# v1-mouse-pins-assigned.net
KiCad netlist of a schematic drawn in EAGLE
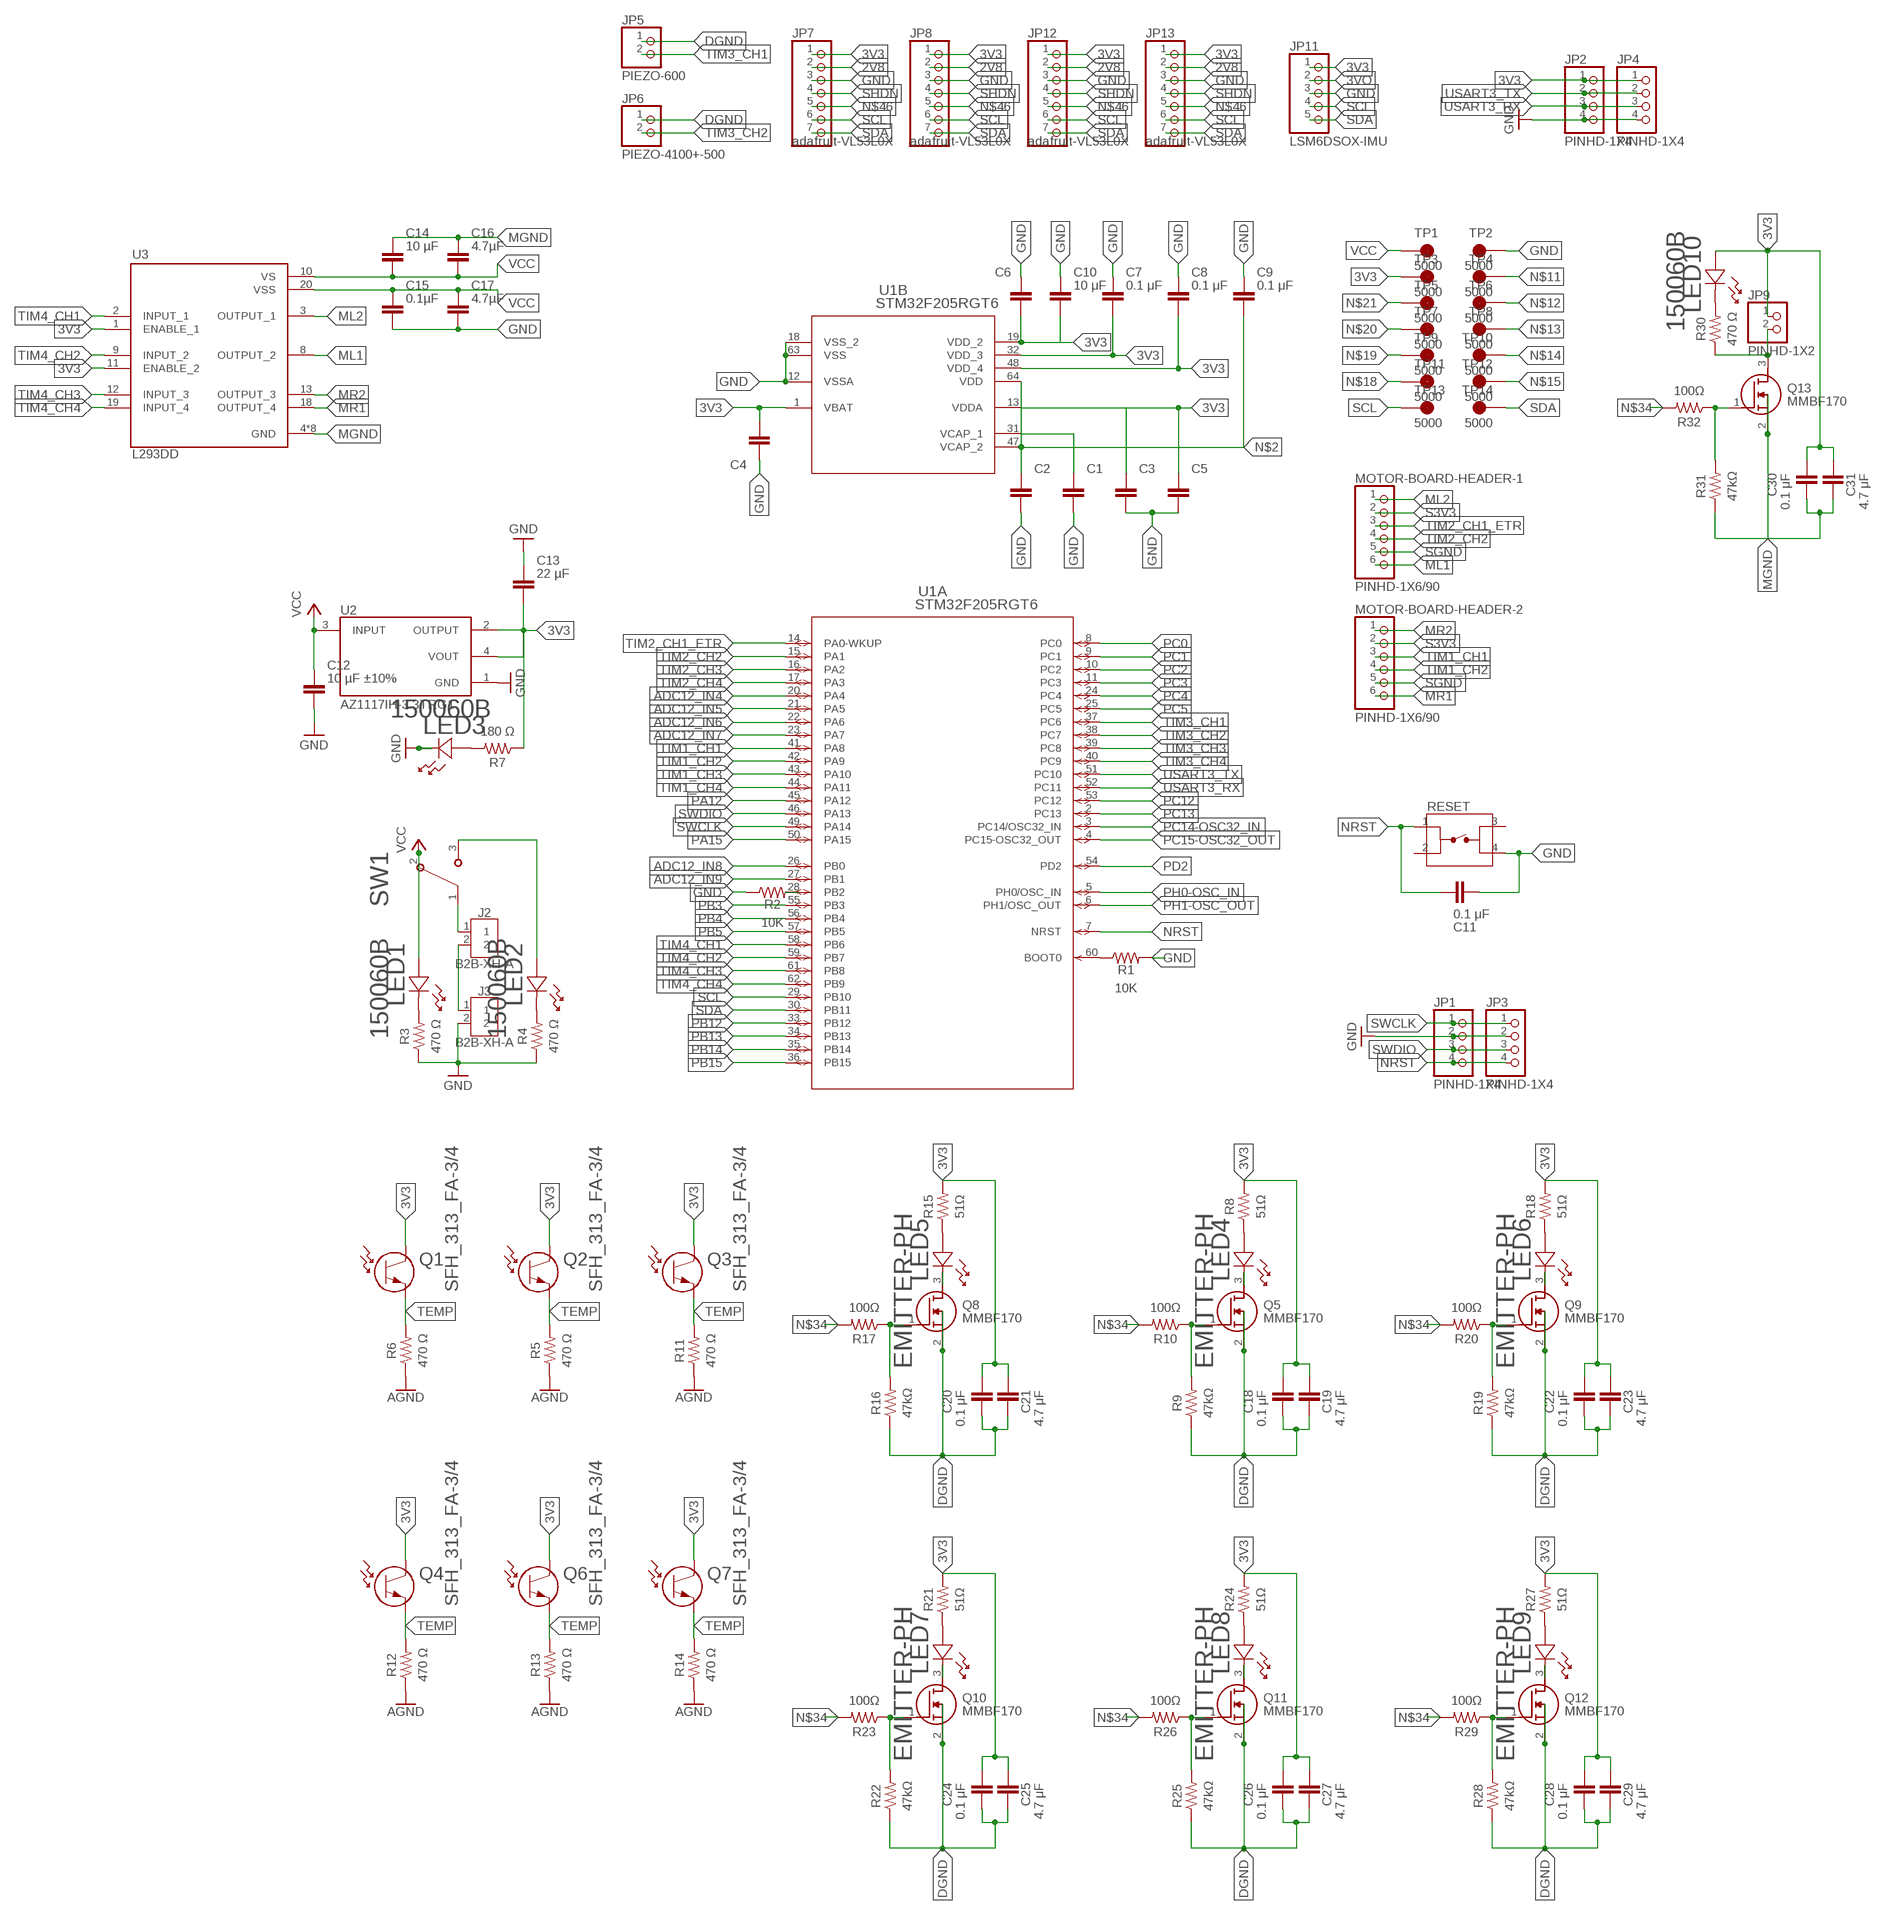
[diagram p0: schematic, sheet 1]

(export (version "E")
  (design (tool "Eeschema 10.0.6"))
  (components
    (comp (ref "C1")
      (value "2.2 μF")
      (footprint "eagle-import:CAPC1608X85")
      (libsource (lib "eagle-import") (part "CCHIP-0603(1608-METRIC)_"))
    )
    (comp (ref "C2")
      (value "2.2 μF")
      (footprint "eagle-import:CAPC1608X85")
      (libsource (lib "eagle-import") (part "CCHIP-0603(1608-METRIC)_"))
    )
    (comp (ref "C3")
      (value "0.1 μF")
      (footprint "eagle-import:CAPC1608X85")
      (libsource (lib "eagle-import") (part "CCHIP-0603(1608-METRIC)_"))
    )
    (comp (ref "C4")
      (value "0.1 μF")
      (footprint "eagle-import:CAPC1608X85")
      (libsource (lib "eagle-import") (part "CCHIP-0603(1608-METRIC)_"))
    )
    (comp (ref "C5")
      (value "1 μF")
      (footprint "eagle-import:CAPC1608X85")
      (libsource (lib "eagle-import") (part "CCHIP-0603(1608-METRIC)_"))
    )
    (comp (ref "C6")
      (value "0.1 μF")
      (footprint "eagle-import:CAPC1608X85")
      (libsource (lib "eagle-import") (part "CCHIP-0603(1608-METRIC)_"))
    )
    (comp (ref "C7")
      (value "0.1 μF")
      (footprint "eagle-import:CAPC1608X85")
      (libsource (lib "eagle-import") (part "Capacitor2_CCHIP-0603(1608-METRIC)_"))
    )
    (comp (ref "C8")
      (value "0.1 μF")
      (footprint "eagle-import:CAPC1608X85")
      (libsource (lib "eagle-import") (part "Capacitor2_CCHIP-0603(1608-METRIC)_"))
    )
    (comp (ref "C9")
      (value "0.1 μF")
      (footprint "eagle-import:CAPC1608X85")
      (libsource (lib "eagle-import") (part "Capacitor2_CCHIP-0603(1608-METRIC)_"))
    )
    (comp (ref "C10")
      (value "10 μF")
      (footprint "eagle-import:CAPC1608X85")
      (libsource (lib "eagle-import") (part "Capacitor2_CCHIP-0603(1608-METRIC)_"))
    )
    (comp (ref "C11")
      (value "0.1 μF")
      (footprint "eagle-import:CAPC1608X85")
      (libsource (lib "eagle-import") (part "Capacitor2_CCHIP-0603(1608-METRIC)_"))
    )
    (comp (ref "C12")
      (value "10 µF ±10%")
      (footprint "eagle-import:CAPC1608X85")
      (libsource (lib "eagle-import") (part "CCHIP-0603(1608-METRIC)_"))
    )
    (comp (ref "C13")
      (value "22 µF")
      (footprint "eagle-import:CAPC1608X85")
      (libsource (lib "eagle-import") (part "CCHIP-0603(1608-METRIC)_"))
    )
    (comp (ref "C14")
      (value "10 µF")
      (footprint "eagle-import:CAPC1608X85")
      (libsource (lib "eagle-import") (part "CCHIP-0603(1608-METRIC)_"))
    )
    (comp (ref "C15")
      (value "0.1µF")
      (footprint "eagle-import:CAPC1608X85")
      (libsource (lib "eagle-import") (part "CCHIP-0603(1608-METRIC)_"))
    )
    (comp (ref "C16")
      (value "4.7µF")
      (footprint "eagle-import:CAPC1608X85")
      (libsource (lib "eagle-import") (part "CCHIP-0603(1608-METRIC)_"))
    )
    (comp (ref "C17")
      (value "4.7µF")
      (footprint "eagle-import:CAPC1608X85")
      (libsource (lib "eagle-import") (part "CCHIP-0603(1608-METRIC)_"))
    )
    (comp (ref "C18")
      (value "0.1 μF")
      (footprint "eagle-import:CAPC1608X85")
      (libsource (lib "eagle-import") (part "Capacitor2_CCHIP-0603(1608-METRIC)_"))
    )
    (comp (ref "C19")
      (value "4.7 μF")
      (footprint "eagle-import:CAPC1608X85")
      (libsource (lib "eagle-import") (part "Capacitor2_CCHIP-0603(1608-METRIC)_"))
    )
    (comp (ref "C20")
      (value "0.1 μF")
      (footprint "eagle-import:CAPC1608X85")
      (libsource (lib "eagle-import") (part "Capacitor2_CCHIP-0603(1608-METRIC)_"))
    )
    (comp (ref "C21")
      (value "4.7 μF")
      (footprint "eagle-import:CAPC1608X85")
      (libsource (lib "eagle-import") (part "Capacitor2_CCHIP-0603(1608-METRIC)_"))
    )
    (comp (ref "C22")
      (value "0.1 μF")
      (footprint "eagle-import:CAPC1608X85")
      (libsource (lib "eagle-import") (part "Capacitor2_CCHIP-0603(1608-METRIC)_"))
    )
    (comp (ref "C23")
      (value "4.7 μF")
      (footprint "eagle-import:CAPC1608X85")
      (libsource (lib "eagle-import") (part "Capacitor2_CCHIP-0603(1608-METRIC)_"))
    )
    (comp (ref "C24")
      (value "0.1 μF")
      (footprint "eagle-import:CAPC1608X85")
      (libsource (lib "eagle-import") (part "Capacitor2_CCHIP-0603(1608-METRIC)_"))
    )
    (comp (ref "C25")
      (value "4.7 μF")
      (footprint "eagle-import:CAPC1608X85")
      (libsource (lib "eagle-import") (part "Capacitor2_CCHIP-0603(1608-METRIC)_"))
    )
    (comp (ref "C26")
      (value "0.1 μF")
      (footprint "eagle-import:CAPC1608X85")
      (libsource (lib "eagle-import") (part "Capacitor2_CCHIP-0603(1608-METRIC)_"))
    )
    (comp (ref "C27")
      (value "4.7 μF")
      (footprint "eagle-import:CAPC1608X85")
      (libsource (lib "eagle-import") (part "Capacitor2_CCHIP-0603(1608-METRIC)_"))
    )
    (comp (ref "C28")
      (value "0.1 μF")
      (footprint "eagle-import:CAPC1608X85")
      (libsource (lib "eagle-import") (part "Capacitor2_CCHIP-0603(1608-METRIC)_"))
    )
    (comp (ref "C29")
      (value "4.7 μF")
      (footprint "eagle-import:CAPC1608X85")
      (libsource (lib "eagle-import") (part "Capacitor2_CCHIP-0603(1608-METRIC)_"))
    )
    (comp (ref "C30")
      (value "0.1 μF")
      (footprint "eagle-import:CAPC1608X85")
      (libsource (lib "eagle-import") (part "Capacitor2_CCHIP-0603(1608-METRIC)_"))
    )
    (comp (ref "C31")
      (value "4.7 μF")
      (footprint "eagle-import:CAPC1608X85")
      (libsource (lib "eagle-import") (part "Capacitor2_CCHIP-0603(1608-METRIC)_"))
    )
    (comp (ref "J2")
      (value "B2B-XH-A")
      (footprint "eagle-import:B2B-XH-A")
      (fields
        (field (name "MANUFACTURER") "JST Sales America Inc. ")
        (field (name "MPN") "B2B-XH-A(LF)(SN) ")
      )
      (libsource (lib "eagle-import") (part "B2B-XH-A"))
    )
    (comp (ref "J3")
      (value "B2B-XH-A")
      (footprint "eagle-import:B2B-XH-A")
      (fields
        (field (name "MANUFACTURER") "JST Sales America Inc. ")
        (field (name "MPN") "B2B-XH-A(LF)(SN) ")
      )
      (libsource (lib "eagle-import") (part "B2B-XH-A"))
    )
    (comp (ref "JP1")
      (value "PINHD-1X4")
      (footprint "eagle-import:1X04")
      (fields (field (name "MANUFACTURER") "Generic"))
      (libsource (lib "eagle-import") (part "PINHD-1X4"))
    )
    (comp (ref "JP2")
      (value "PINHD-1X4")
      (footprint "eagle-import:1X04")
      (fields (field (name "MANUFACTURER") "Generic"))
      (libsource (lib "eagle-import") (part "PINHD-1X4"))
    )
    (comp (ref "JP3")
      (value "PINHD-1X4")
      (footprint "eagle-import:1X04")
      (fields (field (name "MANUFACTURER") "Generic"))
      (libsource (lib "eagle-import") (part "PINHD-1X4"))
    )
    (comp (ref "JP4")
      (value "PINHD-1X4")
      (footprint "eagle-import:1X04")
      (fields (field (name "MANUFACTURER") "Generic"))
      (libsource (lib "eagle-import") (part "PINHD-1X4"))
    )
    (comp (ref "JP5")
      (value "PIEZO-600")
      (footprint "eagle-import:1X02_90")
      (fields (field (name "MANUFACTURER") "Generic"))
      (libsource (lib "eagle-import") (part "PINHD-1X2/90"))
    )
    (comp (ref "JP6")
      (value "PIEZO-4100+-500")
      (footprint "eagle-import:1X02_90")
      (fields (field (name "MANUFACTURER") "Generic"))
      (libsource (lib "eagle-import") (part "PINHD-1X2/90"))
    )
    (comp (ref "JP7")
      (value "adafruit-VL53L0X")
      (footprint "eagle-import:1X07_90")
      (fields (field (name "MANUFACTURER") "Generic"))
      (libsource (lib "eagle-import") (part "PINHD-1X7/90"))
    )
    (comp (ref "JP8")
      (value "adafruit-VL53L0X")
      (footprint "eagle-import:1X07_90")
      (fields (field (name "MANUFACTURER") "Generic"))
      (libsource (lib "eagle-import") (part "PINHD-1X7/90"))
    )
    (comp (ref "JP9")
      (value "PINHD-1X2")
      (footprint "eagle-import:1X02")
      (fields (field (name "MANUFACTURER") "Generic"))
      (libsource (lib "eagle-import") (part "PINHD-1X2"))
    )
    (comp (ref "JP11")
      (value "LSM6DSOX-IMU")
      (footprint "eagle-import:1_05X2MM")
      (fields (field (name "MANUFACTURER") "Generic"))
      (libsource (lib "eagle-import") (part "PINHD-1X55X2MM"))
    )
    (comp (ref "JP12")
      (value "adafruit-VL53L0X")
      (footprint "eagle-import:1X07_90")
      (fields (field (name "MANUFACTURER") "Generic"))
      (libsource (lib "eagle-import") (part "PINHD-1X7/90"))
    )
    (comp (ref "JP13")
      (value "adafruit-VL53L0X")
      (footprint "eagle-import:1X07_90")
      (fields (field (name "MANUFACTURER") "Generic"))
      (libsource (lib "eagle-import") (part "PINHD-1X7/90"))
    )
    (comp (ref "LED1")
      (value "150060B")
      (footprint "eagle-import:LED_150060B_WRE-L")
      (fields
        (field (name "MANUFACTURER_PART_NUMBER") "150060VS55040")
        (field (name "COPYRIGHT") "Copyright (C) 2024 Ultra Librarian. All rights reserved.")
      )
      (libsource (lib "eagle-import") (part "150060VS55040LED_150060B_WRE-L"))
    )
    (comp (ref "LED2")
      (value "150060B")
      (footprint "eagle-import:LED_150060B_WRE-L")
      (fields
        (field (name "MANUFACTURER_PART_NUMBER") "150060VS55040")
        (field (name "COPYRIGHT") "Copyright (C) 2024 Ultra Librarian. All rights reserved.")
      )
      (libsource (lib "eagle-import") (part "150060VS55040LED_150060B_WRE-L"))
    )
    (comp (ref "LED3")
      (value "150060B")
      (footprint "eagle-import:LED_150060B_WRE-L")
      (fields
        (field (name "MANUFACTURER_PART_NUMBER") "150060VS55040")
        (field (name "COPYRIGHT") "Copyright (C) 2024 Ultra Librarian. All rights reserved.")
      )
      (libsource (lib "eagle-import") (part "150060VS55040LED_150060B_WRE-L"))
    )
    (comp (ref "LED4")
      (value "EMITTER-PH")
      (footprint "eagle-import:LED_B1911PG--20D000514U1930_01")
      (fields
        (field (name "MANUFACTURER_PART_NUMBER") "B1911PG--20D000514U1930")
        (field (name "COPYRIGHT") "Copyright (C) 2024 Ultra Librarian. All rights reserved.")
      )
      (libsource (lib "eagle-import") (part "B1911PG--20D000514U1930LED_B1911PG--20D000514U1930_01"))
    )
    (comp (ref "LED5")
      (value "EMITTER-PH")
      (footprint "eagle-import:LED_B1911PG--20D000514U1930_01")
      (fields
        (field (name "MANUFACTURER_PART_NUMBER") "B1911PG--20D000514U1930")
        (field (name "COPYRIGHT") "Copyright (C) 2024 Ultra Librarian. All rights reserved.")
      )
      (libsource (lib "eagle-import") (part "B1911PG--20D000514U1930LED_B1911PG--20D000514U1930_01"))
    )
    (comp (ref "LED6")
      (value "EMITTER-PH")
      (footprint "eagle-import:LED_B1911PG--20D000514U1930_01")
      (fields
        (field (name "MANUFACTURER_PART_NUMBER") "B1911PG--20D000514U1930")
        (field (name "COPYRIGHT") "Copyright (C) 2024 Ultra Librarian. All rights reserved.")
      )
      (libsource (lib "eagle-import") (part "B1911PG--20D000514U1930LED_B1911PG--20D000514U1930_01"))
    )
    (comp (ref "LED7")
      (value "EMITTER-PH")
      (footprint "eagle-import:LED_B1911PG--20D000514U1930_01")
      (fields
        (field (name "MANUFACTURER_PART_NUMBER") "B1911PG--20D000514U1930")
        (field (name "COPYRIGHT") "Copyright (C) 2024 Ultra Librarian. All rights reserved.")
      )
      (libsource (lib "eagle-import") (part "B1911PG--20D000514U1930LED_B1911PG--20D000514U1930_01"))
    )
    (comp (ref "LED8")
      (value "EMITTER-PH")
      (footprint "eagle-import:LED_B1911PG--20D000514U1930_01")
      (fields
        (field (name "MANUFACTURER_PART_NUMBER") "B1911PG--20D000514U1930")
        (field (name "COPYRIGHT") "Copyright (C) 2024 Ultra Librarian. All rights reserved.")
      )
      (libsource (lib "eagle-import") (part "B1911PG--20D000514U1930LED_B1911PG--20D000514U1930_01"))
    )
    (comp (ref "LED9")
      (value "EMITTER-PH")
      (footprint "eagle-import:LED_B1911PG--20D000514U1930_01")
      (fields
        (field (name "MANUFACTURER_PART_NUMBER") "B1911PG--20D000514U1930")
        (field (name "COPYRIGHT") "Copyright (C) 2024 Ultra Librarian. All rights reserved.")
      )
      (libsource (lib "eagle-import") (part "B1911PG--20D000514U1930LED_B1911PG--20D000514U1930_01"))
    )
    (comp (ref "LED10")
      (value "150060B")
      (footprint "eagle-import:LED_150060B_WRE-L")
      (fields
        (field (name "MANUFACTURER_PART_NUMBER") "150060VS55040")
        (field (name "COPYRIGHT") "Copyright (C) 2024 Ultra Librarian. All rights reserved.")
      )
      (libsource (lib "eagle-import") (part "150060VS55040LED_150060B_WRE-L"))
    )
    (comp (ref "MOTOR-BOARD-HEADER-1")
      (value "PINHD-1X6/90")
      (footprint "eagle-import:1X06_90")
      (fields (field (name "MANUFACTURER") "Generic"))
      (libsource (lib "eagle-import") (part "PINHD-1X6/90"))
    )
    (comp (ref "MOTOR-BOARD-HEADER-2")
      (value "PINHD-1X6/90")
      (footprint "eagle-import:1X06_90")
      (fields (field (name "MANUFACTURER") "Generic"))
      (libsource (lib "eagle-import") (part "PINHD-1X6/90"))
    )
    (comp (ref "Q1")
      (value "SFH_313_FA-3/4")
      (footprint "eagle-import:SFH_313_FA-3_4_OSR")
      (fields
        (field (name "MANUFACTURER_PART_NUMBER") "SFH 313 FA-3/4")
        (field (name "COPYRIGHT") "Copyright (C) 2024 Ultra Librarian. All rights reserved.")
      )
      (libsource (lib "eagle-import") (part "SFH_313_FA-3/4SFH_313_FA-3/4_OSR"))
    )
    (comp (ref "Q2")
      (value "SFH_313_FA-3/4")
      (footprint "eagle-import:SFH_313_FA-3_4_OSR")
      (fields
        (field (name "MANUFACTURER_PART_NUMBER") "SFH 313 FA-3/4")
        (field (name "COPYRIGHT") "Copyright (C) 2024 Ultra Librarian. All rights reserved.")
      )
      (libsource (lib "eagle-import") (part "SFH_313_FA-3/4SFH_313_FA-3/4_OSR"))
    )
    (comp (ref "Q3")
      (value "SFH_313_FA-3/4")
      (footprint "eagle-import:SFH_313_FA-3_4_OSR")
      (fields
        (field (name "MANUFACTURER_PART_NUMBER") "SFH 313 FA-3/4")
        (field (name "COPYRIGHT") "Copyright (C) 2024 Ultra Librarian. All rights reserved.")
      )
      (libsource (lib "eagle-import") (part "SFH_313_FA-3/4SFH_313_FA-3/4_OSR"))
    )
    (comp (ref "Q4")
      (value "SFH_313_FA-3/4")
      (footprint "eagle-import:SFH_313_FA-3_4_OSR")
      (fields
        (field (name "MANUFACTURER_PART_NUMBER") "SFH 313 FA-3/4")
        (field (name "COPYRIGHT") "Copyright (C) 2024 Ultra Librarian. All rights reserved.")
      )
      (libsource (lib "eagle-import") (part "SFH_313_FA-3/4SFH_313_FA-3/4_OSR"))
    )
    (comp (ref "Q5")
      (value "MMBF170")
      (footprint "eagle-import:SOT96P237X111-3N")
      (fields (field (name "MOUSER_PART_NUMBER") "512-MMBF170"))
      (libsource (lib "eagle-import") (part "MMBF170"))
    )
    (comp (ref "Q6")
      (value "SFH_313_FA-3/4")
      (footprint "eagle-import:SFH_313_FA-3_4_OSR")
      (fields
        (field (name "MANUFACTURER_PART_NUMBER") "SFH 313 FA-3/4")
        (field (name "COPYRIGHT") "Copyright (C) 2024 Ultra Librarian. All rights reserved.")
      )
      (libsource (lib "eagle-import") (part "SFH_313_FA-3/4SFH_313_FA-3/4_OSR"))
    )
    (comp (ref "Q7")
      (value "SFH_313_FA-3/4")
      (footprint "eagle-import:SFH_313_FA-3_4_OSR")
      (fields
        (field (name "MANUFACTURER_PART_NUMBER") "SFH 313 FA-3/4")
        (field (name "COPYRIGHT") "Copyright (C) 2024 Ultra Librarian. All rights reserved.")
      )
      (libsource (lib "eagle-import") (part "SFH_313_FA-3/4SFH_313_FA-3/4_OSR"))
    )
    (comp (ref "Q8")
      (value "MMBF170")
      (footprint "eagle-import:SOT96P237X111-3N")
      (fields (field (name "MOUSER_PART_NUMBER") "512-MMBF170"))
      (libsource (lib "eagle-import") (part "MMBF170"))
    )
    (comp (ref "Q9")
      (value "MMBF170")
      (footprint "eagle-import:SOT96P237X111-3N")
      (fields (field (name "MOUSER_PART_NUMBER") "512-MMBF170"))
      (libsource (lib "eagle-import") (part "MMBF170"))
    )
    (comp (ref "Q10")
      (value "MMBF170")
      (footprint "eagle-import:SOT96P237X111-3N")
      (fields (field (name "MOUSER_PART_NUMBER") "512-MMBF170"))
      (libsource (lib "eagle-import") (part "MMBF170"))
    )
    (comp (ref "Q11")
      (value "MMBF170")
      (footprint "eagle-import:SOT96P237X111-3N")
      (fields (field (name "MOUSER_PART_NUMBER") "512-MMBF170"))
      (libsource (lib "eagle-import") (part "MMBF170"))
    )
    (comp (ref "Q12")
      (value "MMBF170")
      (footprint "eagle-import:SOT96P237X111-3N")
      (fields (field (name "MOUSER_PART_NUMBER") "512-MMBF170"))
      (libsource (lib "eagle-import") (part "MMBF170"))
    )
    (comp (ref "Q13")
      (value "MMBF170")
      (footprint "eagle-import:SOT96P237X111-3N")
      (fields (field (name "MOUSER_PART_NUMBER") "512-MMBF170"))
      (libsource (lib "eagle-import") (part "MMBF170"))
    )
    (comp (ref "R1")
      (value "10K")
      (footprint "eagle-import:RESC1608X60")
      (libsource (lib "eagle-import") (part "Resistor2_R-USCHIP-0603(1608-METRIC)_"))
    )
    (comp (ref "R2")
      (value "10K")
      (footprint "eagle-import:RESC1608X60")
      (libsource (lib "eagle-import") (part "Resistor2_R-USCHIP-0603(1608-METRIC)_"))
    )
    (comp (ref "R3")
      (value "470 Ω")
      (footprint "eagle-import:RESC1608X60")
      (libsource (lib "eagle-import") (part "R-USCHIP-0603(1608-METRIC)_"))
    )
    (comp (ref "R4")
      (value "470 Ω")
      (footprint "eagle-import:RESC1608X60")
      (libsource (lib "eagle-import") (part "R-USCHIP-0603(1608-METRIC)_"))
    )
    (comp (ref "R5")
      (value "470 Ω")
      (footprint "eagle-import:RESC1608X60")
      (libsource (lib "eagle-import") (part "R-USCHIP-0603(1608-METRIC)_"))
    )
    (comp (ref "R6")
      (value "470 Ω")
      (footprint "eagle-import:RESC1608X60")
      (libsource (lib "eagle-import") (part "R-USCHIP-0603(1608-METRIC)_"))
    )
    (comp (ref "R7")
      (value "180 Ω")
      (footprint "eagle-import:RESC1608X60")
      (libsource (lib "eagle-import") (part "R-USCHIP-0603(1608-METRIC)_"))
    )
    (comp (ref "R8")
      (value "51Ω")
      (footprint "eagle-import:RESC1608X60")
      (libsource (lib "eagle-import") (part "R-USCHIP-0603(1608-METRIC)_"))
    )
    (comp (ref "R9")
      (value "47kΩ")
      (footprint "eagle-import:RESC1608X60")
      (libsource (lib "eagle-import") (part "R-USCHIP-0603(1608-METRIC)_"))
    )
    (comp (ref "R10")
      (value "100Ω")
      (footprint "eagle-import:RESC1608X60")
      (libsource (lib "eagle-import") (part "R-USCHIP-0603(1608-METRIC)_"))
    )
    (comp (ref "R11")
      (value "470 Ω")
      (footprint "eagle-import:RESC1608X60")
      (libsource (lib "eagle-import") (part "R-USCHIP-0603(1608-METRIC)_"))
    )
    (comp (ref "R12")
      (value "470 Ω")
      (footprint "eagle-import:RESC1608X60")
      (libsource (lib "eagle-import") (part "R-USCHIP-0603(1608-METRIC)_"))
    )
    (comp (ref "R13")
      (value "470 Ω")
      (footprint "eagle-import:RESC1608X60")
      (libsource (lib "eagle-import") (part "R-USCHIP-0603(1608-METRIC)_"))
    )
    (comp (ref "R14")
      (value "470 Ω")
      (footprint "eagle-import:RESC1608X60")
      (libsource (lib "eagle-import") (part "R-USCHIP-0603(1608-METRIC)_"))
    )
    (comp (ref "R15")
      (value "51Ω")
      (footprint "eagle-import:RESC1608X60")
      (libsource (lib "eagle-import") (part "R-USCHIP-0603(1608-METRIC)_"))
    )
    (comp (ref "R16")
      (value "47kΩ")
      (footprint "eagle-import:RESC1608X60")
      (libsource (lib "eagle-import") (part "R-USCHIP-0603(1608-METRIC)_"))
    )
    (comp (ref "R17")
      (value "100Ω")
      (footprint "eagle-import:RESC1608X60")
      (libsource (lib "eagle-import") (part "R-USCHIP-0603(1608-METRIC)_"))
    )
    (comp (ref "R18")
      (value "51Ω")
      (footprint "eagle-import:RESC1608X60")
      (libsource (lib "eagle-import") (part "R-USCHIP-0603(1608-METRIC)_"))
    )
    (comp (ref "R19")
      (value "47kΩ")
      (footprint "eagle-import:RESC1608X60")
      (libsource (lib "eagle-import") (part "R-USCHIP-0603(1608-METRIC)_"))
    )
    (comp (ref "R20")
      (value "100Ω")
      (footprint "eagle-import:RESC1608X60")
      (libsource (lib "eagle-import") (part "R-USCHIP-0603(1608-METRIC)_"))
    )
    (comp (ref "R21")
      (value "51Ω")
      (footprint "eagle-import:RESC1608X60")
      (libsource (lib "eagle-import") (part "R-USCHIP-0603(1608-METRIC)_"))
    )
    (comp (ref "R22")
      (value "47kΩ")
      (footprint "eagle-import:RESC1608X60")
      (libsource (lib "eagle-import") (part "R-USCHIP-0603(1608-METRIC)_"))
    )
    (comp (ref "R23")
      (value "100Ω")
      (footprint "eagle-import:RESC1608X60")
      (libsource (lib "eagle-import") (part "R-USCHIP-0603(1608-METRIC)_"))
    )
    (comp (ref "R24")
      (value "51Ω")
      (footprint "eagle-import:RESC1608X60")
      (libsource (lib "eagle-import") (part "R-USCHIP-0603(1608-METRIC)_"))
    )
    (comp (ref "R25")
      (value "47kΩ")
      (footprint "eagle-import:RESC1608X60")
      (libsource (lib "eagle-import") (part "R-USCHIP-0603(1608-METRIC)_"))
    )
    (comp (ref "R26")
      (value "100Ω")
      (footprint "eagle-import:RESC1608X60")
      (libsource (lib "eagle-import") (part "R-USCHIP-0603(1608-METRIC)_"))
    )
    (comp (ref "R27")
      (value "51Ω")
      (footprint "eagle-import:RESC1608X60")
      (libsource (lib "eagle-import") (part "R-USCHIP-0603(1608-METRIC)_"))
    )
    (comp (ref "R28")
      (value "47kΩ")
      (footprint "eagle-import:RESC1608X60")
      (libsource (lib "eagle-import") (part "R-USCHIP-0603(1608-METRIC)_"))
    )
    (comp (ref "R29")
      (value "100Ω")
      (footprint "eagle-import:RESC1608X60")
      (libsource (lib "eagle-import") (part "R-USCHIP-0603(1608-METRIC)_"))
    )
    (comp (ref "R30")
      (value "470 Ω")
      (footprint "eagle-import:RESC1608X60")
      (libsource (lib "eagle-import") (part "R-USCHIP-0603(1608-METRIC)_"))
    )
    (comp (ref "R31")
      (value "47kΩ")
      (footprint "eagle-import:RESC1608X60")
      (libsource (lib "eagle-import") (part "R-USCHIP-0603(1608-METRIC)_"))
    )
    (comp (ref "R32")
      (value "100Ω")
      (footprint "eagle-import:RESC1608X60")
      (libsource (lib "eagle-import") (part "R-USCHIP-0603(1608-METRIC)_"))
    )
    (comp (ref "RESET")
      (value "FSM4JSMA")
      (footprint "eagle-import:TE_FSM4JSMA")
      (fields
        (field (name "COMMENT") "4-1437565-1")
        (field (name "DIGI-KEY_PART_NUMBER") "450-1759-2-ND")
        (field (name "MF") "TE Connectivity")
      )
      (libsource (lib "eagle-import") (part "FSM4JSMA"))
    )
    (comp (ref "SW1")
      (value "EG1218SW_1218_EWI")
      (footprint "eagle-import:SW_1218_EWI")
      (fields
        (field (name "MANUFACTURER_PART_NUMBER") "EG1218")
        (field (name "COPYRIGHT") "Copyright (C) 2024 Ultra Librarian. All rights reserved.")
      )
      (libsource (lib "eagle-import") (part "EG1218SW_1218_EWI"))
    )
    (comp (ref "TP1")
      (value "5000")
      (footprint "eagle-import:KEYSTONE_5000")
      (fields (field (name "MF") "Keystone Electronics"))
      (libsource (lib "eagle-import") (part "5000"))
    )
    (comp (ref "TP2")
      (value "5000")
      (footprint "eagle-import:KEYSTONE_5000")
      (fields (field (name "MF") "Keystone Electronics"))
      (libsource (lib "eagle-import") (part "5000"))
    )
    (comp (ref "TP3")
      (value "5000")
      (footprint "eagle-import:KEYSTONE_5000")
      (fields (field (name "MF") "Keystone Electronics"))
      (libsource (lib "eagle-import") (part "5000"))
    )
    (comp (ref "TP4")
      (value "5000")
      (footprint "eagle-import:KEYSTONE_5000")
      (fields (field (name "MF") "Keystone Electronics"))
      (libsource (lib "eagle-import") (part "5000"))
    )
    (comp (ref "TP5")
      (value "5000")
      (footprint "eagle-import:KEYSTONE_5000")
      (fields (field (name "MF") "Keystone Electronics"))
      (libsource (lib "eagle-import") (part "5000"))
    )
    (comp (ref "TP6")
      (value "5000")
      (footprint "eagle-import:KEYSTONE_5000")
      (fields (field (name "MF") "Keystone Electronics"))
      (libsource (lib "eagle-import") (part "5000"))
    )
    (comp (ref "TP7")
      (value "5000")
      (footprint "eagle-import:KEYSTONE_5000")
      (fields (field (name "MF") "Keystone Electronics"))
      (libsource (lib "eagle-import") (part "5000"))
    )
    (comp (ref "TP8")
      (value "5000")
      (footprint "eagle-import:KEYSTONE_5000")
      (fields (field (name "MF") "Keystone Electronics"))
      (libsource (lib "eagle-import") (part "5000"))
    )
    (comp (ref "TP9")
      (value "5000")
      (footprint "eagle-import:KEYSTONE_5000")
      (fields (field (name "MF") "Keystone Electronics"))
      (libsource (lib "eagle-import") (part "5000"))
    )
    (comp (ref "TP10")
      (value "5000")
      (footprint "eagle-import:KEYSTONE_5000")
      (fields (field (name "MF") "Keystone Electronics"))
      (libsource (lib "eagle-import") (part "5000"))
    )
    (comp (ref "TP11")
      (value "5000")
      (footprint "eagle-import:KEYSTONE_5000")
      (fields (field (name "MF") "Keystone Electronics"))
      (libsource (lib "eagle-import") (part "5000"))
    )
    (comp (ref "TP12")
      (value "5000")
      (footprint "eagle-import:KEYSTONE_5000")
      (fields (field (name "MF") "Keystone Electronics"))
      (libsource (lib "eagle-import") (part "5000"))
    )
    (comp (ref "TP13")
      (value "5000")
      (footprint "eagle-import:KEYSTONE_5000")
      (fields (field (name "MF") "Keystone Electronics"))
      (libsource (lib "eagle-import") (part "5000"))
    )
    (comp (ref "TP14")
      (value "5000")
      (footprint "eagle-import:KEYSTONE_5000")
      (fields (field (name "MF") "Keystone Electronics"))
      (libsource (lib "eagle-import") (part "5000"))
    )
    (comp (ref "U1")
      (value "STM32F205RGT6")
      (footprint "eagle-import:LQFP64-10X10MM")
      (fields (field (name "COPYRIGHT") "Copyright (C) 2021 Ultra Librarian. All rights reserved."))
      (libsource (lib "eagle-import") (part "STM32F205RGT6"))
    )
    (comp (ref "U2")
      (value "AZ1117IH-3.3TRG1")
      (footprint "eagle-import:SOT230P700X185-4N")
      (fields (field (name "MF") "Diodes Inc."))
      (libsource (lib "eagle-import") (part "AZ1117IH-3.3TRG1"))
    )
    (comp (ref "U3")
      (value "L293DD")
      (footprint "eagle-import:SOIC127P1032X265-20N")
      (fields (field (name "MANUFACTURER") "STMicroelectronics"))
      (libsource (lib "eagle-import") (part "L293DD"))
    )
  )
  (nets
    (net (code "1") (name "2V8") (class "Default")
      (node (ref "JP12") (pin "2") (pinfunction "2_2") (pintype "passive"))
      (node (ref "JP13") (pin "2") (pinfunction "2_2") (pintype "passive"))
      (node (ref "JP7") (pin "2") (pinfunction "2_2") (pintype "passive"))
      (node (ref "JP8") (pin "2") (pinfunction "2_2") (pintype "passive"))
    )
    (net (code "2") (name "3V3") (class "Default")
      (node (ref "C10") (pin "2") (pinfunction "2_2") (pintype "passive"))
      (node (ref "C13") (pin "2") (pinfunction "2_2") (pintype "passive"))
      (node (ref "C18") (pin "2") (pinfunction "2_2") (pintype "passive"))
      (node (ref "C19") (pin "2") (pinfunction "2_2") (pintype "passive"))
      (node (ref "C20") (pin "2") (pinfunction "2_2") (pintype "passive"))
      (node (ref "C21") (pin "2") (pinfunction "2_2") (pintype "passive"))
      (node (ref "C22") (pin "2") (pinfunction "2_2") (pintype "passive"))
      (node (ref "C23") (pin "2") (pinfunction "2_2") (pintype "passive"))
      (node (ref "C24") (pin "2") (pinfunction "2_2") (pintype "passive"))
      (node (ref "C25") (pin "2") (pinfunction "2_2") (pintype "passive"))
      (node (ref "C26") (pin "2") (pinfunction "2_2") (pintype "passive"))
      (node (ref "C27") (pin "2") (pinfunction "2_2") (pintype "passive"))
      (node (ref "C28") (pin "2") (pinfunction "2_2") (pintype "passive"))
      (node (ref "C29") (pin "2") (pinfunction "2_2") (pintype "passive"))
      (node (ref "C3") (pin "1") (pinfunction "1_1") (pintype "passive"))
      (node (ref "C30") (pin "2") (pinfunction "2_2") (pintype "passive"))
      (node (ref "C31") (pin "2") (pinfunction "2_2") (pintype "passive"))
      (node (ref "C4") (pin "2") (pinfunction "2_2") (pintype "passive"))
      (node (ref "C5") (pin "1") (pinfunction "1_1") (pintype "passive"))
      (node (ref "C6") (pin "2") (pinfunction "2_2") (pintype "passive"))
      (node (ref "C7") (pin "2") (pinfunction "2_2") (pintype "passive"))
      (node (ref "C8") (pin "2") (pinfunction "2_2") (pintype "passive"))
      (node (ref "JP11") (pin "1") (pinfunction "1_1") (pintype "passive"))
      (node (ref "JP12") (pin "1") (pinfunction "1_1") (pintype "passive"))
      (node (ref "JP13") (pin "1") (pinfunction "1_1") (pintype "passive"))
      (node (ref "JP2") (pin "1") (pinfunction "1_1") (pintype "passive"))
      (node (ref "JP4") (pin "1") (pinfunction "1_1") (pintype "passive"))
      (node (ref "JP7") (pin "1") (pinfunction "1_1") (pintype "passive"))
      (node (ref "JP8") (pin "1") (pinfunction "1_1") (pintype "passive"))
      (node (ref "JP9") (pin "1") (pinfunction "1_1") (pintype "passive"))
      (node (ref "LED10") (pin "2") (pinfunction "2_2") (pintype "passive"))
      (node (ref "Q1") (pin "2") (pinfunction "2_2") (pintype "passive"))
      (node (ref "Q2") (pin "2") (pinfunction "2_2") (pintype "passive"))
      (node (ref "Q3") (pin "2") (pinfunction "2_2") (pintype "passive"))
      (node (ref "Q4") (pin "2") (pinfunction "2_2") (pintype "passive"))
      (node (ref "Q6") (pin "2") (pinfunction "2_2") (pintype "passive"))
      (node (ref "Q7") (pin "2") (pinfunction "2_2") (pintype "passive"))
      (node (ref "R15") (pin "2") (pinfunction "2_2") (pintype "passive"))
      (node (ref "R18") (pin "2") (pinfunction "2_2") (pintype "passive"))
      (node (ref "R21") (pin "2") (pinfunction "2_2") (pintype "passive"))
      (node (ref "R24") (pin "2") (pinfunction "2_2") (pintype "passive"))
      (node (ref "R27") (pin "2") (pinfunction "2_2") (pintype "passive"))
      (node (ref "R7") (pin "1") (pinfunction "1_1") (pintype "passive"))
      (node (ref "R8") (pin "2") (pinfunction "2_2") (pintype "passive"))
      (node (ref "TP3") (pin "TP") (pinfunction "TP_TP") (pintype "passive"))
      (node (ref "U1") (pin "1") (pinfunction "VBAT_1") (pintype "power_in"))
      (node (ref "U1") (pin "13") (pinfunction "VDDA_13") (pintype "power_in"))
      (node (ref "U1") (pin "19") (pinfunction "VDD_2_19") (pintype "power_in"))
      (node (ref "U1") (pin "32") (pinfunction "VDD_3_32") (pintype "power_in"))
      (node (ref "U1") (pin "48") (pinfunction "VDD_4_48") (pintype "power_in"))
      (node (ref "U2") (pin "2") (pinfunction "OUTPUT_2") (pintype "output"))
      (node (ref "U2") (pin "4") (pinfunction "VOUT_4") (pintype "output"))
      (node (ref "U3") (pin "1") (pinfunction "ENABLE_1_1") (pintype "input"))
      (node (ref "U3") (pin "11") (pinfunction "ENABLE_2_11") (pintype "input"))
    )
    (net (code "3") (name "3VO") (class "Default")
      (node (ref "JP11") (pin "2") (pinfunction "2_2") (pintype "passive"))
    )
    (net (code "4") (name "ADC12_IN4") (class "Default")
      (node (ref "U1") (pin "20") (pinfunction "PA4_20") (pintype "bidirectional"))
    )
    (net (code "5") (name "ADC12_IN5") (class "Default")
      (node (ref "U1") (pin "21") (pinfunction "PA5_21") (pintype "bidirectional"))
    )
    (net (code "6") (name "ADC12_IN6") (class "Default")
      (node (ref "U1") (pin "22") (pinfunction "PA6_22") (pintype "bidirectional"))
    )
    (net (code "7") (name "ADC12_IN7") (class "Default")
      (node (ref "U1") (pin "23") (pinfunction "PA7_23") (pintype "bidirectional"))
    )
    (net (code "8") (name "ADC12_IN8") (class "Default")
      (node (ref "U1") (pin "26") (pinfunction "PB0_26") (pintype "bidirectional"))
    )
    (net (code "9") (name "ADC12_IN9") (class "Default")
      (node (ref "U1") (pin "27") (pinfunction "PB1_27") (pintype "bidirectional"))
    )
    (net (code "10") (name "AGND") (class "Default")
      (node (ref "R11") (pin "1") (pinfunction "1_1") (pintype "passive"))
      (node (ref "R12") (pin "1") (pinfunction "1_1") (pintype "passive"))
      (node (ref "R13") (pin "1") (pinfunction "1_1") (pintype "passive"))
      (node (ref "R14") (pin "1") (pinfunction "1_1") (pintype "passive"))
      (node (ref "R5") (pin "1") (pinfunction "1_1") (pintype "passive"))
      (node (ref "R6") (pin "1") (pinfunction "1_1") (pintype "passive"))
    )
    (net (code "11") (name "DGND") (class "Default")
      (node (ref "C18") (pin "1") (pinfunction "1_1") (pintype "passive"))
      (node (ref "C19") (pin "1") (pinfunction "1_1") (pintype "passive"))
      (node (ref "C20") (pin "1") (pinfunction "1_1") (pintype "passive"))
      (node (ref "C21") (pin "1") (pinfunction "1_1") (pintype "passive"))
      (node (ref "C22") (pin "1") (pinfunction "1_1") (pintype "passive"))
      (node (ref "C23") (pin "1") (pinfunction "1_1") (pintype "passive"))
      (node (ref "C24") (pin "1") (pinfunction "1_1") (pintype "passive"))
      (node (ref "C25") (pin "1") (pinfunction "1_1") (pintype "passive"))
      (node (ref "C26") (pin "1") (pinfunction "1_1") (pintype "passive"))
      (node (ref "C27") (pin "1") (pinfunction "1_1") (pintype "passive"))
      (node (ref "C28") (pin "1") (pinfunction "1_1") (pintype "passive"))
      (node (ref "C29") (pin "1") (pinfunction "1_1") (pintype "passive"))
      (node (ref "C30") (pin "1") (pinfunction "1_1") (pintype "passive"))
      (node (ref "C31") (pin "1") (pinfunction "1_1") (pintype "passive"))
      (node (ref "JP5") (pin "1") (pinfunction "1_1") (pintype "passive"))
      (node (ref "JP6") (pin "1") (pinfunction "1_1") (pintype "passive"))
      (node (ref "Q10") (pin "2") (pinfunction "S_2") (pintype "bidirectional"))
      (node (ref "Q11") (pin "2") (pinfunction "S_2") (pintype "bidirectional"))
      (node (ref "Q12") (pin "2") (pinfunction "S_2") (pintype "bidirectional"))
      (node (ref "Q5") (pin "2") (pinfunction "S_2") (pintype "bidirectional"))
      (node (ref "Q8") (pin "2") (pinfunction "S_2") (pintype "bidirectional"))
      (node (ref "Q9") (pin "2") (pinfunction "S_2") (pintype "bidirectional"))
      (node (ref "R16") (pin "1") (pinfunction "1_1") (pintype "passive"))
      (node (ref "R19") (pin "1") (pinfunction "1_1") (pintype "passive"))
      (node (ref "R22") (pin "1") (pinfunction "1_1") (pintype "passive"))
      (node (ref "R25") (pin "1") (pinfunction "1_1") (pintype "passive"))
      (node (ref "R28") (pin "1") (pinfunction "1_1") (pintype "passive"))
      (node (ref "R31") (pin "1") (pinfunction "1_1") (pintype "passive"))
      (node (ref "R9") (pin "1") (pinfunction "1_1") (pintype "passive"))
    )
    (net (code "12") (name "GND") (class "Default")
      (node (ref "C1") (pin "2") (pinfunction "2_2") (pintype "passive"))
      (node (ref "C10") (pin "1") (pinfunction "1_1") (pintype "passive"))
      (node (ref "C11") (pin "1") (pinfunction "1_1") (pintype "passive"))
      (node (ref "C12") (pin "2") (pinfunction "2_2") (pintype "passive"))
      (node (ref "C13") (pin "1") (pinfunction "1_1") (pintype "passive"))
      (node (ref "C15") (pin "2") (pinfunction "2_2") (pintype "passive"))
      (node (ref "C17") (pin "2") (pinfunction "2_2") (pintype "passive"))
      (node (ref "C2") (pin "2") (pinfunction "2_2") (pintype "passive"))
      (node (ref "C3") (pin "2") (pinfunction "2_2") (pintype "passive"))
      (node (ref "C4") (pin "1") (pinfunction "1_1") (pintype "passive"))
      (node (ref "C5") (pin "2") (pinfunction "2_2") (pintype "passive"))
      (node (ref "C6") (pin "1") (pinfunction "1_1") (pintype "passive"))
      (node (ref "C7") (pin "1") (pinfunction "1_1") (pintype "passive"))
      (node (ref "C8") (pin "1") (pinfunction "1_1") (pintype "passive"))
      (node (ref "C9") (pin "1") (pinfunction "1_1") (pintype "passive"))
      (node (ref "J3") (pin "2") (pinfunction "2_2") (pintype "bidirectional"))
      (node (ref "JP1") (pin "2") (pinfunction "2_2") (pintype "passive"))
      (node (ref "JP11") (pin "3") (pinfunction "3_3") (pintype "passive"))
      (node (ref "JP12") (pin "3") (pinfunction "3_3") (pintype "passive"))
      (node (ref "JP13") (pin "3") (pinfunction "3_3") (pintype "passive"))
      (node (ref "JP2") (pin "4") (pinfunction "4_4") (pintype "passive"))
      (node (ref "JP3") (pin "2") (pinfunction "2_2") (pintype "passive"))
      (node (ref "JP4") (pin "4") (pinfunction "4_4") (pintype "passive"))
      (node (ref "JP7") (pin "3") (pinfunction "3_3") (pintype "passive"))
      (node (ref "JP8") (pin "3") (pinfunction "3_3") (pintype "passive"))
      (node (ref "LED3") (pin "1") (pinfunction "1_1") (pintype "passive"))
      (node (ref "R1") (pin "2") (pinfunction "2_2") (pintype "passive"))
      (node (ref "R2") (pin "1") (pinfunction "1_1") (pintype "passive"))
      (node (ref "R3") (pin "1") (pinfunction "1_1") (pintype "passive"))
      (node (ref "R4") (pin "1") (pinfunction "1_1") (pintype "passive"))
      (node (ref "RESET") (pin "4") (pinfunction "4_4") (pintype "passive"))
      (node (ref "TP2") (pin "TP") (pinfunction "TP_TP") (pintype "passive"))
      (node (ref "U1") (pin "12") (pinfunction "VSSA_12") (pintype "power_in"))
      (node (ref "U1") (pin "18") (pinfunction "VSS_2_18") (pintype "power_in"))
      (node (ref "U1") (pin "63") (pinfunction "VSS_63") (pintype "power_in"))
      (node (ref "U2") (pin "1") (pinfunction "GND_1") (pintype "power_in"))
    )
    (net (code "13") (name "MGND") (class "Default")
      (node (ref "C14") (pin "1") (pinfunction "1_1") (pintype "passive"))
      (node (ref "C16") (pin "1") (pinfunction "1_1") (pintype "passive"))
      (node (ref "Q13") (pin "2") (pinfunction "S_2") (pintype "bidirectional"))
      (node (ref "U3") (pin "14") (pinfunction "GND_14") (pintype "power_in"))
      (node (ref "U3") (pin "15") (pinfunction "GND_15") (pintype "power_in"))
      (node (ref "U3") (pin "16") (pinfunction "GND_16") (pintype "power_in"))
      (node (ref "U3") (pin "17") (pinfunction "GND_17") (pintype "power_in"))
      (node (ref "U3") (pin "4") (pinfunction "GND_4") (pintype "power_in"))
      (node (ref "U3") (pin "5") (pinfunction "GND_5") (pintype "power_in"))
      (node (ref "U3") (pin "6") (pinfunction "GND_6") (pintype "power_in"))
      (node (ref "U3") (pin "7") (pinfunction "GND_7") (pintype "power_in"))
    )
    (net (code "14") (name "ML1") (class "Default")
      (node (ref "MOTOR-BOARD-HEADER-1") (pin "6") (pinfunction "6_6") (pintype "passive"))
      (node (ref "U3") (pin "8") (pinfunction "OUTPUT_2_8") (pintype "output"))
    )
    (net (code "15") (name "ML2") (class "Default")
      (node (ref "MOTOR-BOARD-HEADER-1") (pin "1") (pinfunction "1_1") (pintype "passive"))
      (node (ref "U3") (pin "3") (pinfunction "OUTPUT_1_3") (pintype "output"))
    )
    (net (code "16") (name "MR1") (class "Default")
      (node (ref "MOTOR-BOARD-HEADER-2") (pin "6") (pinfunction "6_6") (pintype "passive"))
      (node (ref "U3") (pin "18") (pinfunction "OUTPUT_4_18") (pintype "output"))
    )
    (net (code "17") (name "MR2") (class "Default")
      (node (ref "MOTOR-BOARD-HEADER-2") (pin "1") (pinfunction "1_1") (pintype "passive"))
      (node (ref "U3") (pin "13") (pinfunction "OUTPUT_3_13") (pintype "output"))
    )
    (net (code "18") (name "N$2") (class "Default")
      (node (ref "C2") (pin "1") (pinfunction "1_1") (pintype "passive"))
      (node (ref "C9") (pin "2") (pinfunction "2_2") (pintype "passive"))
      (node (ref "U1") (pin "47") (pinfunction "VCAP_2_47") (pintype "power_in"))
      (node (ref "U1") (pin "64") (pinfunction "VDD_64") (pintype "power_in"))
    )
    (net (code "19") (name "N$11") (class "Default")
      (node (ref "TP4") (pin "TP") (pinfunction "TP_TP") (pintype "passive"))
    )
    (net (code "20") (name "N$12") (class "Default")
      (node (ref "TP6") (pin "TP") (pinfunction "TP_TP") (pintype "passive"))
    )
    (net (code "21") (name "N$13") (class "Default")
      (node (ref "TP8") (pin "TP") (pinfunction "TP_TP") (pintype "passive"))
    )
    (net (code "22") (name "N$14") (class "Default")
      (node (ref "TP10") (pin "TP") (pinfunction "TP_TP") (pintype "passive"))
    )
    (net (code "23") (name "N$15") (class "Default")
      (node (ref "TP12") (pin "TP") (pinfunction "TP_TP") (pintype "passive"))
    )
    (net (code "24") (name "N$18") (class "Default")
      (node (ref "TP11") (pin "TP") (pinfunction "TP_TP") (pintype "passive"))
    )
    (net (code "25") (name "N$19") (class "Default")
      (node (ref "TP9") (pin "TP") (pinfunction "TP_TP") (pintype "passive"))
    )
    (net (code "26") (name "N$20") (class "Default")
      (node (ref "TP7") (pin "TP") (pinfunction "TP_TP") (pintype "passive"))
    )
    (net (code "27") (name "N$21") (class "Default")
      (node (ref "TP5") (pin "TP") (pinfunction "TP_TP") (pintype "passive"))
    )
    (net (code "28") (name "N$34") (class "Default")
      (node (ref "R10") (pin "2") (pinfunction "2_2") (pintype "passive"))
      (node (ref "R17") (pin "2") (pinfunction "2_2") (pintype "passive"))
      (node (ref "R20") (pin "2") (pinfunction "2_2") (pintype "passive"))
      (node (ref "R23") (pin "2") (pinfunction "2_2") (pintype "passive"))
      (node (ref "R26") (pin "2") (pinfunction "2_2") (pintype "passive"))
      (node (ref "R29") (pin "2") (pinfunction "2_2") (pintype "passive"))
      (node (ref "R32") (pin "2") (pinfunction "2_2") (pintype "passive"))
    )
    (net (code "29") (name "N$46") (class "Default")
      (node (ref "JP12") (pin "5") (pinfunction "5_5") (pintype "passive"))
      (node (ref "JP13") (pin "5") (pinfunction "5_5") (pintype "passive"))
      (node (ref "JP7") (pin "5") (pinfunction "5_5") (pintype "passive"))
      (node (ref "JP8") (pin "5") (pinfunction "5_5") (pintype "passive"))
    )
    (net (code "30") (name "NRST") (class "Default")
      (node (ref "C11") (pin "2") (pinfunction "2_2") (pintype "passive"))
      (node (ref "JP1") (pin "4") (pinfunction "4_4") (pintype "passive"))
      (node (ref "JP3") (pin "4") (pinfunction "4_4") (pintype "passive"))
      (node (ref "RESET") (pin "1") (pinfunction "1_1") (pintype "passive"))
      (node (ref "U1") (pin "7") (pinfunction "NRST_7") (pintype "bidirectional"))
    )
    (net (code "31") (name "Net-(J2-Pad1)") (class "Default")
      (node (ref "J2") (pin "1") (pinfunction "1_1") (pintype "bidirectional"))
      (node (ref "SW1") (pin "1") (pinfunction "1_1") (pintype "passive"))
    )
    (net (code "32") (name "Net-(J2-Pad2)") (class "Default")
      (node (ref "J2") (pin "2") (pinfunction "2_2") (pintype "bidirectional"))
      (node (ref "J3") (pin "1") (pinfunction "1_1") (pintype "bidirectional"))
    )
    (net (code "33") (name "Net-(LED1-Pad1)") (class "Default")
      (node (ref "LED1") (pin "1") (pinfunction "1_1") (pintype "passive"))
      (node (ref "R3") (pin "2") (pinfunction "2_2") (pintype "passive"))
    )
    (net (code "34") (name "Net-(LED2-Pad1)") (class "Default")
      (node (ref "LED2") (pin "1") (pinfunction "1_1") (pintype "passive"))
      (node (ref "R4") (pin "2") (pinfunction "2_2") (pintype "passive"))
    )
    (net (code "35") (name "Net-(LED2-Pad2)") (class "Default")
      (node (ref "LED2") (pin "2") (pinfunction "2_2") (pintype "passive"))
      (node (ref "SW1") (pin "3") (pinfunction "3_3") (pintype "passive"))
    )
    (net (code "36") (name "Net-(LED3-Pad2)") (class "Default")
      (node (ref "LED3") (pin "2") (pinfunction "2_2") (pintype "passive"))
      (node (ref "R7") (pin "2") (pinfunction "2_2") (pintype "passive"))
    )
    (net (code "37") (name "Net-(LED4-Pad2)") (class "Default")
      (node (ref "LED4") (pin "2") (pinfunction "2_2") (pintype "passive"))
      (node (ref "R8") (pin "1") (pinfunction "1_1") (pintype "passive"))
    )
    (net (code "38") (name "Net-(LED5-Pad2)") (class "Default")
      (node (ref "LED5") (pin "2") (pinfunction "2_2") (pintype "passive"))
      (node (ref "R15") (pin "1") (pinfunction "1_1") (pintype "passive"))
    )
    (net (code "39") (name "Net-(LED6-Pad2)") (class "Default")
      (node (ref "LED6") (pin "2") (pinfunction "2_2") (pintype "passive"))
      (node (ref "R18") (pin "1") (pinfunction "1_1") (pintype "passive"))
    )
    (net (code "40") (name "Net-(LED7-Pad2)") (class "Default")
      (node (ref "LED7") (pin "2") (pinfunction "2_2") (pintype "passive"))
      (node (ref "R21") (pin "1") (pinfunction "1_1") (pintype "passive"))
    )
    (net (code "41") (name "Net-(LED8-Pad2)") (class "Default")
      (node (ref "LED8") (pin "2") (pinfunction "2_2") (pintype "passive"))
      (node (ref "R24") (pin "1") (pinfunction "1_1") (pintype "passive"))
    )
    (net (code "42") (name "Net-(LED9-Pad2)") (class "Default")
      (node (ref "LED9") (pin "2") (pinfunction "2_2") (pintype "passive"))
      (node (ref "R27") (pin "1") (pinfunction "1_1") (pintype "passive"))
    )
    (net (code "43") (name "Net-(LED10-Pad1)") (class "Default")
      (node (ref "LED10") (pin "1") (pinfunction "1_1") (pintype "passive"))
      (node (ref "R30") (pin "2") (pinfunction "2_2") (pintype "passive"))
    )
    (net (code "44") (name "Net-(Q5-D)") (class "Default")
      (node (ref "LED4") (pin "1") (pinfunction "1_1") (pintype "passive"))
      (node (ref "Q5") (pin "3") (pinfunction "D_3") (pintype "bidirectional"))
    )
    (net (code "45") (name "Net-(Q5-G)") (class "Default")
      (node (ref "Q5") (pin "1") (pinfunction "G_1") (pintype "bidirectional"))
      (node (ref "R10") (pin "1") (pinfunction "1_1") (pintype "passive"))
      (node (ref "R9") (pin "2") (pinfunction "2_2") (pintype "passive"))
    )
    (net (code "46") (name "Net-(Q8-D)") (class "Default")
      (node (ref "LED5") (pin "1") (pinfunction "1_1") (pintype "passive"))
      (node (ref "Q8") (pin "3") (pinfunction "D_3") (pintype "bidirectional"))
    )
    (net (code "47") (name "Net-(Q8-G)") (class "Default")
      (node (ref "Q8") (pin "1") (pinfunction "G_1") (pintype "bidirectional"))
      (node (ref "R16") (pin "2") (pinfunction "2_2") (pintype "passive"))
      (node (ref "R17") (pin "1") (pinfunction "1_1") (pintype "passive"))
    )
    (net (code "48") (name "Net-(Q9-D)") (class "Default")
      (node (ref "LED6") (pin "1") (pinfunction "1_1") (pintype "passive"))
      (node (ref "Q9") (pin "3") (pinfunction "D_3") (pintype "bidirectional"))
    )
    (net (code "49") (name "Net-(Q9-G)") (class "Default")
      (node (ref "Q9") (pin "1") (pinfunction "G_1") (pintype "bidirectional"))
      (node (ref "R19") (pin "2") (pinfunction "2_2") (pintype "passive"))
      (node (ref "R20") (pin "1") (pinfunction "1_1") (pintype "passive"))
    )
    (net (code "50") (name "Net-(Q10-D)") (class "Default")
      (node (ref "LED7") (pin "1") (pinfunction "1_1") (pintype "passive"))
      (node (ref "Q10") (pin "3") (pinfunction "D_3") (pintype "bidirectional"))
    )
    (net (code "51") (name "Net-(Q10-G)") (class "Default")
      (node (ref "Q10") (pin "1") (pinfunction "G_1") (pintype "bidirectional"))
      (node (ref "R22") (pin "2") (pinfunction "2_2") (pintype "passive"))
      (node (ref "R23") (pin "1") (pinfunction "1_1") (pintype "passive"))
    )
    (net (code "52") (name "Net-(Q11-D)") (class "Default")
      (node (ref "LED8") (pin "1") (pinfunction "1_1") (pintype "passive"))
      (node (ref "Q11") (pin "3") (pinfunction "D_3") (pintype "bidirectional"))
    )
    (net (code "53") (name "Net-(Q11-G)") (class "Default")
      (node (ref "Q11") (pin "1") (pinfunction "G_1") (pintype "bidirectional"))
      (node (ref "R25") (pin "2") (pinfunction "2_2") (pintype "passive"))
      (node (ref "R26") (pin "1") (pinfunction "1_1") (pintype "passive"))
    )
    (net (code "54") (name "Net-(Q12-D)") (class "Default")
      (node (ref "LED9") (pin "1") (pinfunction "1_1") (pintype "passive"))
      (node (ref "Q12") (pin "3") (pinfunction "D_3") (pintype "bidirectional"))
    )
    (net (code "55") (name "Net-(Q12-G)") (class "Default")
      (node (ref "Q12") (pin "1") (pinfunction "G_1") (pintype "bidirectional"))
      (node (ref "R28") (pin "2") (pinfunction "2_2") (pintype "passive"))
      (node (ref "R29") (pin "1") (pinfunction "1_1") (pintype "passive"))
    )
    (net (code "56") (name "Net-(Q13-D)") (class "Default")
      (node (ref "JP9") (pin "2") (pinfunction "2_2") (pintype "passive"))
      (node (ref "Q13") (pin "3") (pinfunction "D_3") (pintype "bidirectional"))
      (node (ref "R30") (pin "1") (pinfunction "1_1") (pintype "passive"))
    )
    (net (code "57") (name "Net-(Q13-G)") (class "Default")
      (node (ref "Q13") (pin "1") (pinfunction "G_1") (pintype "bidirectional"))
      (node (ref "R31") (pin "2") (pinfunction "2_2") (pintype "passive"))
      (node (ref "R32") (pin "1") (pinfunction "1_1") (pintype "passive"))
    )
    (net (code "58") (name "Net-(U1A-BOOT0)") (class "Default")
      (node (ref "R1") (pin "1") (pinfunction "1_1") (pintype "passive"))
      (node (ref "U1") (pin "60") (pinfunction "BOOT0_60") (pintype "input"))
    )
    (net (code "59") (name "Net-(U1A-PB2)") (class "Default")
      (node (ref "R2") (pin "2") (pinfunction "2_2") (pintype "passive"))
      (node (ref "U1") (pin "28") (pinfunction "PB2_28") (pintype "bidirectional"))
    )
    (net (code "60") (name "Net-(U1B-VCAP_1)") (class "Default")
      (node (ref "C1") (pin "1") (pinfunction "1_1") (pintype "passive"))
      (node (ref "U1") (pin "31") (pinfunction "VCAP_1_31") (pintype "power_in"))
    )
    (net (code "61") (name "PA12") (class "Default")
      (node (ref "U1") (pin "45") (pinfunction "PA12_45") (pintype "bidirectional"))
    )
    (net (code "62") (name "PA15") (class "Default")
      (node (ref "U1") (pin "50") (pinfunction "PA15_50") (pintype "bidirectional"))
    )
    (net (code "63") (name "PB3") (class "Default")
      (node (ref "U1") (pin "55") (pinfunction "PB3_55") (pintype "bidirectional"))
    )
    (net (code "64") (name "PB4") (class "Default")
      (node (ref "U1") (pin "56") (pinfunction "PB4_56") (pintype "bidirectional"))
    )
    (net (code "65") (name "PB5") (class "Default")
      (node (ref "U1") (pin "57") (pinfunction "PB5_57") (pintype "bidirectional"))
    )
    (net (code "66") (name "PB12") (class "Default")
      (node (ref "U1") (pin "33") (pinfunction "PB12_33") (pintype "bidirectional"))
    )
    (net (code "67") (name "PB13") (class "Default")
      (node (ref "U1") (pin "34") (pinfunction "PB13_34") (pintype "bidirectional"))
    )
    (net (code "68") (name "PB14") (class "Default")
      (node (ref "U1") (pin "35") (pinfunction "PB14_35") (pintype "bidirectional"))
    )
    (net (code "69") (name "PB15") (class "Default")
      (node (ref "U1") (pin "36") (pinfunction "PB15_36") (pintype "bidirectional"))
    )
    (net (code "70") (name "PC0") (class "Default")
      (node (ref "U1") (pin "8") (pinfunction "PC0_8") (pintype "bidirectional"))
    )
    (net (code "71") (name "PC1") (class "Default")
      (node (ref "U1") (pin "9") (pinfunction "PC1_9") (pintype "bidirectional"))
    )
    (net (code "72") (name "PC2") (class "Default")
      (node (ref "U1") (pin "10") (pinfunction "PC2_10") (pintype "bidirectional"))
    )
    (net (code "73") (name "PC3") (class "Default")
      (node (ref "U1") (pin "11") (pinfunction "PC3_11") (pintype "bidirectional"))
    )
    (net (code "74") (name "PC4") (class "Default")
      (node (ref "U1") (pin "24") (pinfunction "PC4_24") (pintype "bidirectional"))
    )
    (net (code "75") (name "PC5") (class "Default")
      (node (ref "U1") (pin "25") (pinfunction "PC5_25") (pintype "bidirectional"))
    )
    (net (code "76") (name "PC12") (class "Default")
      (node (ref "U1") (pin "53") (pinfunction "PC12_53") (pintype "bidirectional"))
    )
    (net (code "77") (name "PC13") (class "Default")
      (node (ref "U1") (pin "2") (pinfunction "PC13_2") (pintype "bidirectional"))
    )
    (net (code "78") (name "PC14-OSC32_IN") (class "Default")
      (node (ref "U1") (pin "3") (pinfunction "PC14/OSC32_IN_3") (pintype "bidirectional"))
    )
    (net (code "79") (name "PC15-OSC32_OUT") (class "Default")
      (node (ref "U1") (pin "4") (pinfunction "PC15-OSC32_OUT_4") (pintype "bidirectional"))
    )
    (net (code "80") (name "PD2") (class "Default")
      (node (ref "U1") (pin "54") (pinfunction "PD2_54") (pintype "bidirectional"))
    )
    (net (code "81") (name "PH0-OSC_IN") (class "Default")
      (node (ref "U1") (pin "5") (pinfunction "PH0/OSC_IN_5") (pintype "bidirectional"))
    )
    (net (code "82") (name "PH1-OSC_OUT") (class "Default")
      (node (ref "U1") (pin "6") (pinfunction "PH1/OSC_OUT_6") (pintype "bidirectional"))
    )
    (net (code "83") (name "S3V3") (class "Default")
      (node (ref "MOTOR-BOARD-HEADER-1") (pin "2") (pinfunction "2_2") (pintype "passive"))
      (node (ref "MOTOR-BOARD-HEADER-2") (pin "2") (pinfunction "2_2") (pintype "passive"))
    )
    (net (code "84") (name "SCL") (class "Default")
      (node (ref "JP11") (pin "4") (pinfunction "4_4") (pintype "passive"))
      (node (ref "JP12") (pin "6") (pinfunction "6_6") (pintype "passive"))
      (node (ref "JP13") (pin "6") (pinfunction "6_6") (pintype "passive"))
      (node (ref "JP7") (pin "6") (pinfunction "6_6") (pintype "passive"))
      (node (ref "JP8") (pin "6") (pinfunction "6_6") (pintype "passive"))
      (node (ref "TP13") (pin "TP") (pinfunction "TP_TP") (pintype "passive"))
      (node (ref "U1") (pin "29") (pinfunction "PB10_29") (pintype "bidirectional"))
    )
    (net (code "85") (name "SDA") (class "Default")
      (node (ref "JP11") (pin "5") (pinfunction "5_5") (pintype "passive"))
      (node (ref "JP12") (pin "7") (pinfunction "7_7") (pintype "passive"))
      (node (ref "JP13") (pin "7") (pinfunction "7_7") (pintype "passive"))
      (node (ref "JP7") (pin "7") (pinfunction "7_7") (pintype "passive"))
      (node (ref "JP8") (pin "7") (pinfunction "7_7") (pintype "passive"))
      (node (ref "TP14") (pin "TP") (pinfunction "TP_TP") (pintype "passive"))
      (node (ref "U1") (pin "30") (pinfunction "PB11_30") (pintype "bidirectional"))
    )
    (net (code "86") (name "SGND") (class "Default")
      (node (ref "MOTOR-BOARD-HEADER-1") (pin "5") (pinfunction "5_5") (pintype "passive"))
      (node (ref "MOTOR-BOARD-HEADER-2") (pin "5") (pinfunction "5_5") (pintype "passive"))
    )
    (net (code "87") (name "SHDN") (class "Default")
      (node (ref "JP12") (pin "4") (pinfunction "4_4") (pintype "passive"))
      (node (ref "JP13") (pin "4") (pinfunction "4_4") (pintype "passive"))
      (node (ref "JP7") (pin "4") (pinfunction "4_4") (pintype "passive"))
      (node (ref "JP8") (pin "4") (pinfunction "4_4") (pintype "passive"))
    )
    (net (code "88") (name "SWCLK") (class "Default")
      (node (ref "JP1") (pin "1") (pinfunction "1_1") (pintype "passive"))
      (node (ref "JP3") (pin "1") (pinfunction "1_1") (pintype "passive"))
      (node (ref "U1") (pin "49") (pinfunction "PA14_49") (pintype "bidirectional"))
    )
    (net (code "89") (name "SWDIO") (class "Default")
      (node (ref "JP1") (pin "3") (pinfunction "3_3") (pintype "passive"))
      (node (ref "JP3") (pin "3") (pinfunction "3_3") (pintype "passive"))
      (node (ref "U1") (pin "46") (pinfunction "PA13_46") (pintype "bidirectional"))
    )
    (net (code "90") (name "TEMP") (class "Default")
      (node (ref "Q1") (pin "1") (pinfunction "1_1") (pintype "passive"))
      (node (ref "Q2") (pin "1") (pinfunction "1_1") (pintype "passive"))
      (node (ref "Q3") (pin "1") (pinfunction "1_1") (pintype "passive"))
      (node (ref "Q4") (pin "1") (pinfunction "1_1") (pintype "passive"))
      (node (ref "Q6") (pin "1") (pinfunction "1_1") (pintype "passive"))
      (node (ref "Q7") (pin "1") (pinfunction "1_1") (pintype "passive"))
      (node (ref "R11") (pin "2") (pinfunction "2_2") (pintype "passive"))
      (node (ref "R12") (pin "2") (pinfunction "2_2") (pintype "passive"))
      (node (ref "R13") (pin "2") (pinfunction "2_2") (pintype "passive"))
      (node (ref "R14") (pin "2") (pinfunction "2_2") (pintype "passive"))
      (node (ref "R5") (pin "2") (pinfunction "2_2") (pintype "passive"))
      (node (ref "R6") (pin "2") (pinfunction "2_2") (pintype "passive"))
    )
    (net (code "91") (name "TIM1_CH1") (class "Default")
      (node (ref "MOTOR-BOARD-HEADER-2") (pin "3") (pinfunction "3_3") (pintype "passive"))
      (node (ref "U1") (pin "41") (pinfunction "PA8_41") (pintype "bidirectional"))
    )
    (net (code "92") (name "TIM1_CH2") (class "Default")
      (node (ref "MOTOR-BOARD-HEADER-2") (pin "4") (pinfunction "4_4") (pintype "passive"))
      (node (ref "U1") (pin "42") (pinfunction "PA9_42") (pintype "bidirectional"))
    )
    (net (code "93") (name "TIM1_CH3") (class "Default")
      (node (ref "U1") (pin "43") (pinfunction "PA10_43") (pintype "bidirectional"))
    )
    (net (code "94") (name "TIM1_CH4") (class "Default")
      (node (ref "U1") (pin "44") (pinfunction "PA11_44") (pintype "bidirectional"))
    )
    (net (code "95") (name "TIM2_CH1_ETR") (class "Default")
      (node (ref "MOTOR-BOARD-HEADER-1") (pin "3") (pinfunction "3_3") (pintype "passive"))
      (node (ref "U1") (pin "14") (pinfunction "PA0-WKUP_14") (pintype "bidirectional"))
    )
    (net (code "96") (name "TIM2_CH2") (class "Default")
      (node (ref "MOTOR-BOARD-HEADER-1") (pin "4") (pinfunction "4_4") (pintype "passive"))
      (node (ref "U1") (pin "15") (pinfunction "PA1_15") (pintype "bidirectional"))
    )
    (net (code "97") (name "TIM2_CH3") (class "Default")
      (node (ref "U1") (pin "16") (pinfunction "PA2_16") (pintype "bidirectional"))
    )
    (net (code "98") (name "TIM2_CH4") (class "Default")
      (node (ref "U1") (pin "17") (pinfunction "PA3_17") (pintype "bidirectional"))
    )
    (net (code "99") (name "TIM3_CH1") (class "Default")
      (node (ref "JP5") (pin "2") (pinfunction "2_2") (pintype "passive"))
      (node (ref "U1") (pin "37") (pinfunction "PC6_37") (pintype "bidirectional"))
    )
    (net (code "100") (name "TIM3_CH2") (class "Default")
      (node (ref "JP6") (pin "2") (pinfunction "2_2") (pintype "passive"))
      (node (ref "U1") (pin "38") (pinfunction "PC7_38") (pintype "bidirectional"))
    )
    (net (code "101") (name "TIM3_CH3") (class "Default")
      (node (ref "U1") (pin "39") (pinfunction "PC8_39") (pintype "bidirectional"))
    )
    (net (code "102") (name "TIM3_CH4") (class "Default")
      (node (ref "U1") (pin "40") (pinfunction "PC9_40") (pintype "bidirectional"))
    )
    (net (code "103") (name "TIM4_CH1") (class "Default")
      (node (ref "U1") (pin "58") (pinfunction "PB6_58") (pintype "bidirectional"))
      (node (ref "U3") (pin "2") (pinfunction "INPUT_1_2") (pintype "input"))
    )
    (net (code "104") (name "TIM4_CH2") (class "Default")
      (node (ref "U1") (pin "59") (pinfunction "PB7_59") (pintype "bidirectional"))
      (node (ref "U3") (pin "9") (pinfunction "INPUT_2_9") (pintype "input"))
    )
    (net (code "105") (name "TIM4_CH3") (class "Default")
      (node (ref "U1") (pin "61") (pinfunction "PB8_61") (pintype "bidirectional"))
      (node (ref "U3") (pin "12") (pinfunction "INPUT_3_12") (pintype "input"))
    )
    (net (code "106") (name "TIM4_CH4") (class "Default")
      (node (ref "U1") (pin "62") (pinfunction "PB9_62") (pintype "bidirectional"))
      (node (ref "U3") (pin "19") (pinfunction "INPUT_4_19") (pintype "input"))
    )
    (net (code "107") (name "USART3_RX") (class "Default")
      (node (ref "JP2") (pin "3") (pinfunction "3_3") (pintype "passive"))
      (node (ref "JP4") (pin "3") (pinfunction "3_3") (pintype "passive"))
      (node (ref "U1") (pin "52") (pinfunction "PC11_52") (pintype "bidirectional"))
    )
    (net (code "108") (name "USART3_TX") (class "Default")
      (node (ref "JP2") (pin "2") (pinfunction "2_2") (pintype "passive"))
      (node (ref "JP4") (pin "2") (pinfunction "2_2") (pintype "passive"))
      (node (ref "U1") (pin "51") (pinfunction "PC10_51") (pintype "bidirectional"))
    )
    (net (code "109") (name "VCC") (class "Default")
      (node (ref "C12") (pin "1") (pinfunction "1_1") (pintype "passive"))
      (node (ref "C14") (pin "2") (pinfunction "2_2") (pintype "passive"))
      (node (ref "C15") (pin "1") (pinfunction "1_1") (pintype "passive"))
      (node (ref "C16") (pin "2") (pinfunction "2_2") (pintype "passive"))
      (node (ref "C17") (pin "1") (pinfunction "1_1") (pintype "passive"))
      (node (ref "LED1") (pin "2") (pinfunction "2_2") (pintype "passive"))
      (node (ref "SW1") (pin "2") (pinfunction "2_2") (pintype "passive"))
      (node (ref "TP1") (pin "TP") (pinfunction "TP_TP") (pintype "passive"))
      (node (ref "U2") (pin "3") (pinfunction "INPUT_3") (pintype "input"))
      (node (ref "U3") (pin "10") (pinfunction "VS_10") (pintype "power_in"))
      (node (ref "U3") (pin "20") (pinfunction "VSS_20") (pintype "power_in"))
    )
    (net (code "110") (name "unconnected-(RESET-Pad2)") (class "Default")
      (node (ref "RESET") (pin "2") (pinfunction "2_2") (pintype "passive"))
    )
    (net (code "111") (name "unconnected-(RESET-Pad3)") (class "Default")
      (node (ref "RESET") (pin "3") (pinfunction "3_3") (pintype "passive"))
    )
  )
)
